# 11_-Power_Input_and_Regulators.net
KiCad netlist of a schematic drawn in Altium Designer
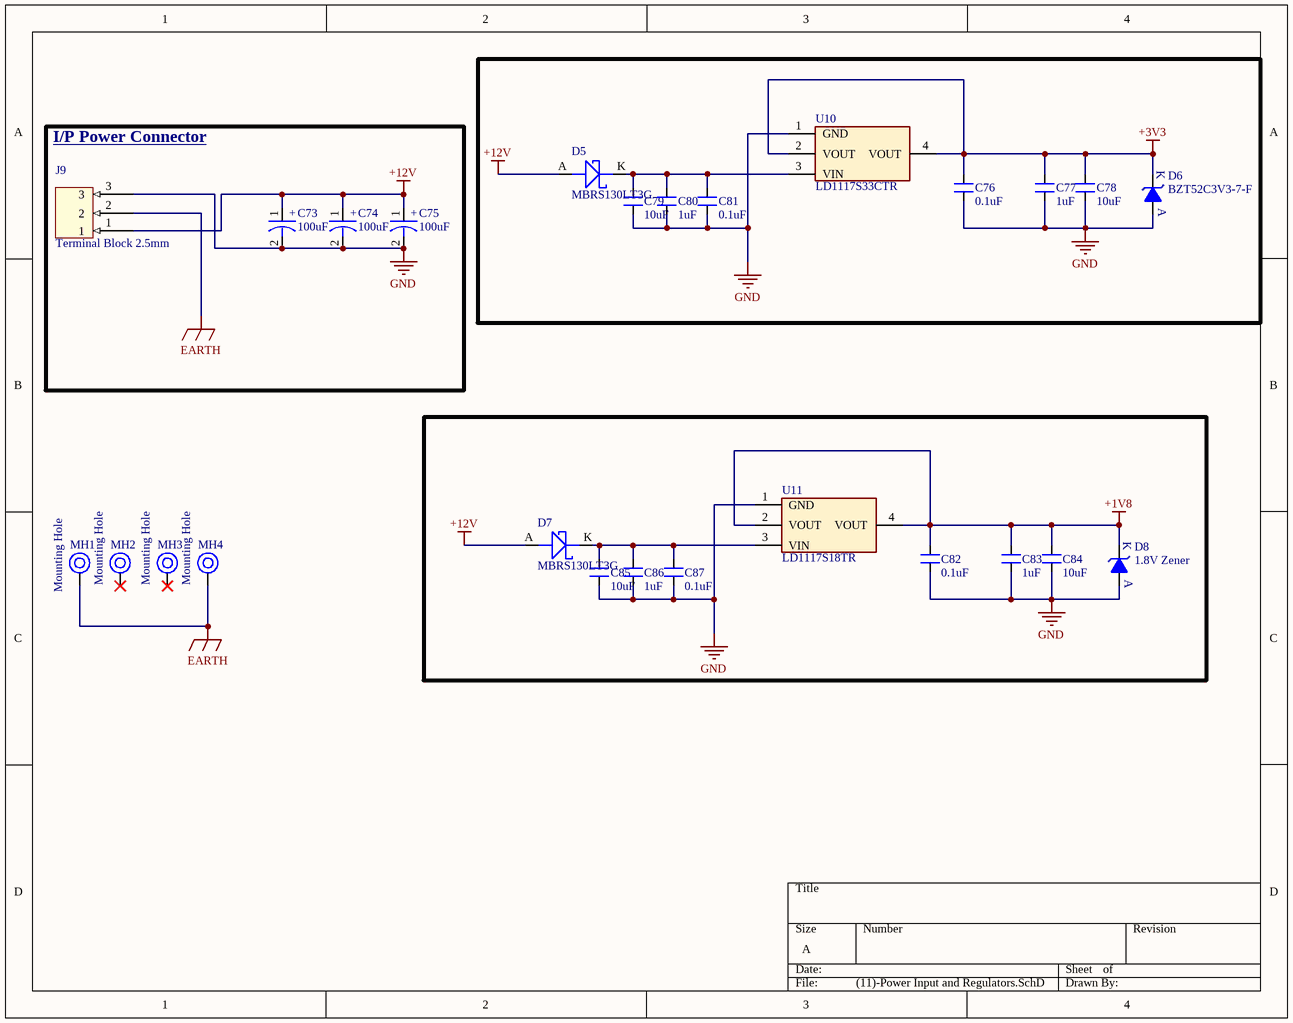
[diagram p0: (11)-Power Input and Regulators.SchDoc]

(export (version "E")
  (design (tool "Eeschema 10.0.6"))
  (components
    (comp (ref "C73")
      (value "100uF")
      (footprint "ACAP_P305_D393_H393_RAD")
      (description "100µF 50V Aluminum Polymer Capacitor Radial, Can - SMD 28mOhm 4000 Hrs @ 125°C")
      (fields
        (field (name "MANUFACTURER") "Nichicon")
        (field (name "MANUFACTURER PART NUMBER") "GYA1H101MCQ1GS")
      )
      (libsource (lib "ESTEEMPCBLIB") (part "CAP-P_100uF-50V-20%-RAD"))
    )
    (comp (ref "C74")
      (value "100uF")
      (footprint "ACAP_P305_D393_H393_RAD")
      (description "100µF 50V Aluminum Polymer Capacitor Radial, Can - SMD 28mOhm 4000 Hrs @ 125°C")
      (fields
        (field (name "MANUFACTURER") "Nichicon")
        (field (name "MANUFACTURER PART NUMBER") "GYA1H101MCQ1GS")
      )
      (libsource (lib "ESTEEMPCBLIB") (part "CAP-P_100uF-50V-20%-RAD"))
    )
    (comp (ref "C75")
      (value "100uF")
      (footprint "ACAP_P305_D393_H393_RAD")
      (description "100µF 50V Aluminum Polymer Capacitor Radial, Can - SMD 28mOhm 4000 Hrs @ 125°C")
      (fields
        (field (name "MANUFACTURER") "Nichicon")
        (field (name "MANUFACTURER PART NUMBER") "GYA1H101MCQ1GS")
      )
      (libsource (lib "ESTEEMPCBLIB") (part "CAP-P_100uF-50V-20%-RAD"))
    )
    (comp (ref "C76")
      (value "0.1uF")
      (footprint "CAP_0805")
      (description "0.1µF ±10% 50V Ceramic Capacitor X7R 0805 (2012 Metric)")
      (fields
        (field (name "MANUFACTURER") "Samsung")
        (field (name "MANUFACTURER PART NUMBER") "CL21B104KBCNNNC")
      )
      (libsource (lib "ESTEEMPCBLIB") (part "CAP_0.1uF-50V-10%-0805"))
    )
    (comp (ref "C77")
      (value "1uF")
      (footprint "CAP_0805")
      (description "1µF ±5% 50V Ceramic Capacitor X7R 0805 (2012 Metric)")
      (fields
        (field (name "MANUFACTURER") "Samsung")
        (field (name "MANUFACTURER PART NUMBER") "CC0805JKX7R9BB105")
      )
      (libsource (lib "ESTEEMPCBLIB") (part "CAP_1uF-50V-5%-0805"))
    )
    (comp (ref "C78")
      (value "10uF")
      (footprint "CAP_1206")
      (description "10µF ±10% 50V Ceramic Capacitor X7R 1206 (3216 Metric)")
      (fields
        (field (name "MANUFACTURER") "KEMET")
        (field (name "MANUFACTURER PART NUMBER") "CL31B106KBHNNNE")
      )
      (libsource (lib "ESTEEMPCBLIB") (part "CAP_10uF-50V-10%-1206"))
    )
    (comp (ref "C79")
      (value "10uF")
      (footprint "CAP_1206")
      (description "10µF ±10% 50V Ceramic Capacitor X7R 1206 (3216 Metric)")
      (fields
        (field (name "MANUFACTURER") "KEMET")
        (field (name "MANUFACTURER PART NUMBER") "CL31B106KBHNNNE")
      )
      (libsource (lib "ESTEEMPCBLIB") (part "CAP_10uF-50V-10%-1206"))
    )
    (comp (ref "C80")
      (value "1uF")
      (footprint "CAP_0805")
      (description "1µF ±5% 50V Ceramic Capacitor X7R 0805 (2012 Metric)")
      (fields
        (field (name "MANUFACTURER") "Samsung")
        (field (name "MANUFACTURER PART NUMBER") "CC0805JKX7R9BB105")
      )
      (libsource (lib "ESTEEMPCBLIB") (part "CAP_1uF-50V-5%-0805"))
    )
    (comp (ref "C81")
      (value "0.1uF")
      (footprint "CAP_0805")
      (description "0.1µF ±10% 50V Ceramic Capacitor X7R 0805 (2012 Metric)")
      (fields
        (field (name "MANUFACTURER") "Samsung")
        (field (name "MANUFACTURER PART NUMBER") "CL21B104KBCNNNC")
      )
      (libsource (lib "ESTEEMPCBLIB") (part "CAP_0.1uF-50V-10%-0805"))
    )
    (comp (ref "C82")
      (value "0.1uF")
      (footprint "CAP_0805")
      (description "0.1µF ±10% 50V Ceramic Capacitor X7R 0805 (2012 Metric)")
      (fields
        (field (name "MANUFACTURER") "Samsung")
        (field (name "MANUFACTURER PART NUMBER") "CL21B104KBCNNNC")
      )
      (libsource (lib "ESTEEMPCBLIB") (part "CAP_0.1uF-50V-10%-0805"))
    )
    (comp (ref "C83")
      (value "1uF")
      (footprint "CAP_0805")
      (description "1µF ±5% 50V Ceramic Capacitor X7R 0805 (2012 Metric)")
      (fields
        (field (name "MANUFACTURER") "Samsung")
        (field (name "MANUFACTURER PART NUMBER") "CC0805JKX7R9BB105")
      )
      (libsource (lib "ESTEEMPCBLIB") (part "CAP_1uF-50V-5%-0805"))
    )
    (comp (ref "C84")
      (value "10uF")
      (footprint "CAP_1206")
      (description "10µF ±10% 50V Ceramic Capacitor X7R 1206 (3216 Metric)")
      (fields
        (field (name "MANUFACTURER") "KEMET")
        (field (name "MANUFACTURER PART NUMBER") "CL31B106KBHNNNE")
      )
      (libsource (lib "ESTEEMPCBLIB") (part "CAP_10uF-50V-10%-1206"))
    )
    (comp (ref "C85")
      (value "10uF")
      (footprint "CAP_1206")
      (description "10µF ±10% 50V Ceramic Capacitor X7R 1206 (3216 Metric)")
      (fields
        (field (name "MANUFACTURER") "KEMET")
        (field (name "MANUFACTURER PART NUMBER") "CL31B106KBHNNNE")
      )
      (libsource (lib "ESTEEMPCBLIB") (part "CAP_10uF-50V-10%-1206"))
    )
    (comp (ref "C86")
      (value "1uF")
      (footprint "CAP_0805")
      (description "1µF ±5% 50V Ceramic Capacitor X7R 0805 (2012 Metric)")
      (fields
        (field (name "MANUFACTURER") "Samsung")
        (field (name "MANUFACTURER PART NUMBER") "CC0805JKX7R9BB105")
      )
      (libsource (lib "ESTEEMPCBLIB") (part "CAP_1uF-50V-5%-0805"))
    )
    (comp (ref "C87")
      (value "0.1uF")
      (footprint "CAP_0805")
      (description "0.1µF ±10% 50V Ceramic Capacitor X7R 0805 (2012 Metric)")
      (fields
        (field (name "MANUFACTURER") "Samsung")
        (field (name "MANUFACTURER PART NUMBER") "CL21B104KBCNNNC")
      )
      (libsource (lib "ESTEEMPCBLIB") (part "CAP_0.1uF-50V-10%-0805"))
    )
    (comp (ref "D5")
      (value "MBRS130LT3G")
      (footprint "DIO_SMB_DO-214AA")
      (description "Diode Schottky 30V 2A Surface Mount SMB")
      (fields (field (name "MANUFACTURER") "ON Semiconductor"))
      (libsource (lib "ESTEEMPCBLIB") (part "DIO-S_445mV-30V-2A-SMB"))
    )
    (comp (ref "D6")
      (value "BZT52C3V3-7-F")
      (footprint "DIO_SOD-123")
      (description "Zener Diode 3.3V 500mW ±6% Surface Mount SOD-123")
      (fields (field (name "MANUFACTURER") "Diodes Incorporated"))
      (libsource (lib "ESTEEMPCBLIB") (part "DIO-Z_3.3V-500mW-SOD123"))
    )
    (comp (ref "D7")
      (value "MBRS130LT3G")
      (footprint "DIO_SMB_DO-214AA")
      (description "Diode Schottky 30V 2A Surface Mount SMB")
      (fields (field (name "MANUFACTURER") "ON Semiconductor"))
      (libsource (lib "ESTEEMPCBLIB") (part "DIO-S_445mV-30V-2A-SMB"))
    )
    (comp (ref "D8")
      (value "1.8V Zener")
      (footprint "DIO_DO-213AB_SMD")
      (description "Zener Diode 1.8V 500mW ±5% Surface Mount DO-213AA")
      (libsource (lib "ESTEEMPCBLIB") (part "DIO-Z_1.8V-500mW-DO213AA"))
    )
    (comp (ref "J9")
      (value "Terminal Block 2.5mm")
      (footprint "CON3_100_TB_TH_ST")
      (description "3 Pins, 1 Row 2.54mm Pitch, straight Connector, male")
      (fields
        (field (name "MANUFACTURER PART NUMBER") "1725669")
        (field (name "MANUFACTURER") "Phoenix Contact")
      )
      (libsource (lib "ESTEEMPCBLIB") (part "CON-TB_3X1-100-ST-TH"))
    )
    (comp (ref "MH1")
      (value "Mounting Hole")
      (footprint "MOUNTING")
      (fields (field (name "MANUFACTURER PART NUMBER") "NA"))
      (libsource (lib "ESTEEMPCBLIB") (part "MH_3.5H_6D"))
    )
    (comp (ref "MH2")
      (value "Mounting Hole")
      (footprint "MOUNTING")
      (fields (field (name "MANUFACTURER PART NUMBER") "NA"))
      (libsource (lib "ESTEEMPCBLIB") (part "MH_3.5H_6D"))
    )
    (comp (ref "MH3")
      (value "Mounting Hole")
      (footprint "MOUNTING")
      (fields (field (name "MANUFACTURER PART NUMBER") "NA"))
      (libsource (lib "ESTEEMPCBLIB") (part "MH_3.5H_6D"))
    )
    (comp (ref "MH4")
      (value "Mounting Hole")
      (footprint "MOUNTING")
      (fields (field (name "MANUFACTURER PART NUMBER") "NA"))
      (libsource (lib "ESTEEMPCBLIB") (part "MH_3.5H_6D"))
    )
    (comp (ref "U10")
      (value "LD1117S33CTR")
      (footprint "SOT223_3")
      (description "Linear Voltage Regulator IC 1 Output 800mA SOT-223")
      (fields (field (name "MANUFACTURER") "STMicroelectronics"))
      (libsource (lib "ESTEEMPCBLIB") (part "REG_15V-3.3V-0.9A-12W-SOT223"))
    )
    (comp (ref "U11")
      (value "LD1117S18TR")
      (footprint "SOT223_3")
      (description "LDO Voltage Regulators 1.8V 0.8A Positive")
      (fields (field (name "MANUFACTURER") "STMicroelectronics"))
      (libsource (lib "ESTEEMPCBLIB") (part "REG_15V-1.8V-0.8A-1.4W-SOT223"))
    )
  )
  (nets
    (net (code "1") (name "+1V8") (class "Default")
      (node (ref "C82") (pin "2") (pinfunction "2_2") (pintype "passive"))
      (node (ref "C83") (pin "2") (pinfunction "2_2") (pintype "passive"))
      (node (ref "C84") (pin "2") (pinfunction "2_2") (pintype "passive"))
      (node (ref "D8") (pin "K") (pinfunction "K_K") (pintype "passive"))
      (node (ref "U11") (pin "2") (pinfunction "VOUT_2") (pintype "passive"))
      (node (ref "U11") (pin "4") (pinfunction "VOUT_4") (pintype "passive"))
    )
    (net (code "2") (name "+3V3") (class "Default")
      (node (ref "C76") (pin "2") (pinfunction "2_2") (pintype "passive"))
      (node (ref "C77") (pin "2") (pinfunction "2_2") (pintype "passive"))
      (node (ref "C78") (pin "2") (pinfunction "2_2") (pintype "passive"))
      (node (ref "D6") (pin "K") (pinfunction "K_K") (pintype "passive"))
      (node (ref "U10") (pin "2") (pinfunction "VOUT_2") (pintype "passive"))
      (node (ref "U10") (pin "4") (pinfunction "VOUT_4") (pintype "passive"))
    )
    (net (code "3") (name "+12V") (class "Default")
      (node (ref "C73") (pin "1") (pinfunction "1_1") (pintype "passive"))
      (node (ref "C74") (pin "1") (pinfunction "1_1") (pintype "passive"))
      (node (ref "C75") (pin "1") (pinfunction "1_1") (pintype "passive"))
      (node (ref "D5") (pin "A") (pinfunction "A_A") (pintype "passive"))
      (node (ref "D7") (pin "A") (pinfunction "A_A") (pintype "passive"))
      (node (ref "J9") (pin "1") (pinfunction "1_1") (pintype "input"))
    )
    (net (code "4") (name "EARTH") (class "Default")
      (node (ref "J9") (pin "2") (pinfunction "2_2") (pintype "input"))
      (node (ref "MH1") (pin "1") (pinfunction "1_1") (pintype "passive"))
      (node (ref "MH4") (pin "1") (pinfunction "1_1") (pintype "passive"))
    )
    (net (code "5") (name "GND") (class "Default")
      (node (ref "C73") (pin "2") (pinfunction "2_2") (pintype "passive"))
      (node (ref "C74") (pin "2") (pinfunction "2_2") (pintype "passive"))
      (node (ref "C75") (pin "2") (pinfunction "2_2") (pintype "passive"))
      (node (ref "C76") (pin "1") (pinfunction "1_1") (pintype "passive"))
      (node (ref "C77") (pin "1") (pinfunction "1_1") (pintype "passive"))
      (node (ref "C78") (pin "1") (pinfunction "1_1") (pintype "passive"))
      (node (ref "C79") (pin "1") (pinfunction "1_1") (pintype "passive"))
      (node (ref "C80") (pin "1") (pinfunction "1_1") (pintype "passive"))
      (node (ref "C81") (pin "1") (pinfunction "1_1") (pintype "passive"))
      (node (ref "C82") (pin "1") (pinfunction "1_1") (pintype "passive"))
      (node (ref "C83") (pin "1") (pinfunction "1_1") (pintype "passive"))
      (node (ref "C84") (pin "1") (pinfunction "1_1") (pintype "passive"))
      (node (ref "C85") (pin "1") (pinfunction "1_1") (pintype "passive"))
      (node (ref "C86") (pin "1") (pinfunction "1_1") (pintype "passive"))
      (node (ref "C87") (pin "1") (pinfunction "1_1") (pintype "passive"))
      (node (ref "D6") (pin "A") (pinfunction "A_A") (pintype "passive"))
      (node (ref "D8") (pin "A") (pinfunction "A_A") (pintype "passive"))
      (node (ref "J9") (pin "3") (pinfunction "3_3") (pintype "input"))
      (node (ref "U10") (pin "1") (pinfunction "GND_1") (pintype "passive"))
      (node (ref "U11") (pin "1") (pinfunction "GND_1") (pintype "passive"))
    )
    (net (code "6") (name "Net-(U10-VIN)") (class "Default")
      (node (ref "C79") (pin "2") (pinfunction "2_2") (pintype "passive"))
      (node (ref "C80") (pin "2") (pinfunction "2_2") (pintype "passive"))
      (node (ref "C81") (pin "2") (pinfunction "2_2") (pintype "passive"))
      (node (ref "D5") (pin "K") (pinfunction "K_K") (pintype "passive"))
      (node (ref "U10") (pin "3") (pinfunction "VIN_3") (pintype "passive"))
    )
    (net (code "7") (name "Net-(U11-VIN)") (class "Default")
      (node (ref "C85") (pin "2") (pinfunction "2_2") (pintype "passive"))
      (node (ref "C86") (pin "2") (pinfunction "2_2") (pintype "passive"))
      (node (ref "C87") (pin "2") (pinfunction "2_2") (pintype "passive"))
      (node (ref "D7") (pin "K") (pinfunction "K_K") (pintype "passive"))
      (node (ref "U11") (pin "3") (pinfunction "VIN_3") (pintype "passive"))
    )
    (net (code "8") (name "unconnected-(MH2-Pad1)") (class "Default")
      (node (ref "MH2") (pin "1") (pinfunction "1_1") (pintype "passive+no_connect"))
    )
    (net (code "9") (name "unconnected-(MH3-Pad1)") (class "Default")
      (node (ref "MH3") (pin "1") (pinfunction "1_1") (pintype "passive+no_connect"))
    )
  )
)
